# Copy_of_Prophesse_Sensor_v_1_5.net
KiCad netlist of a schematic drawn in Altium Designer
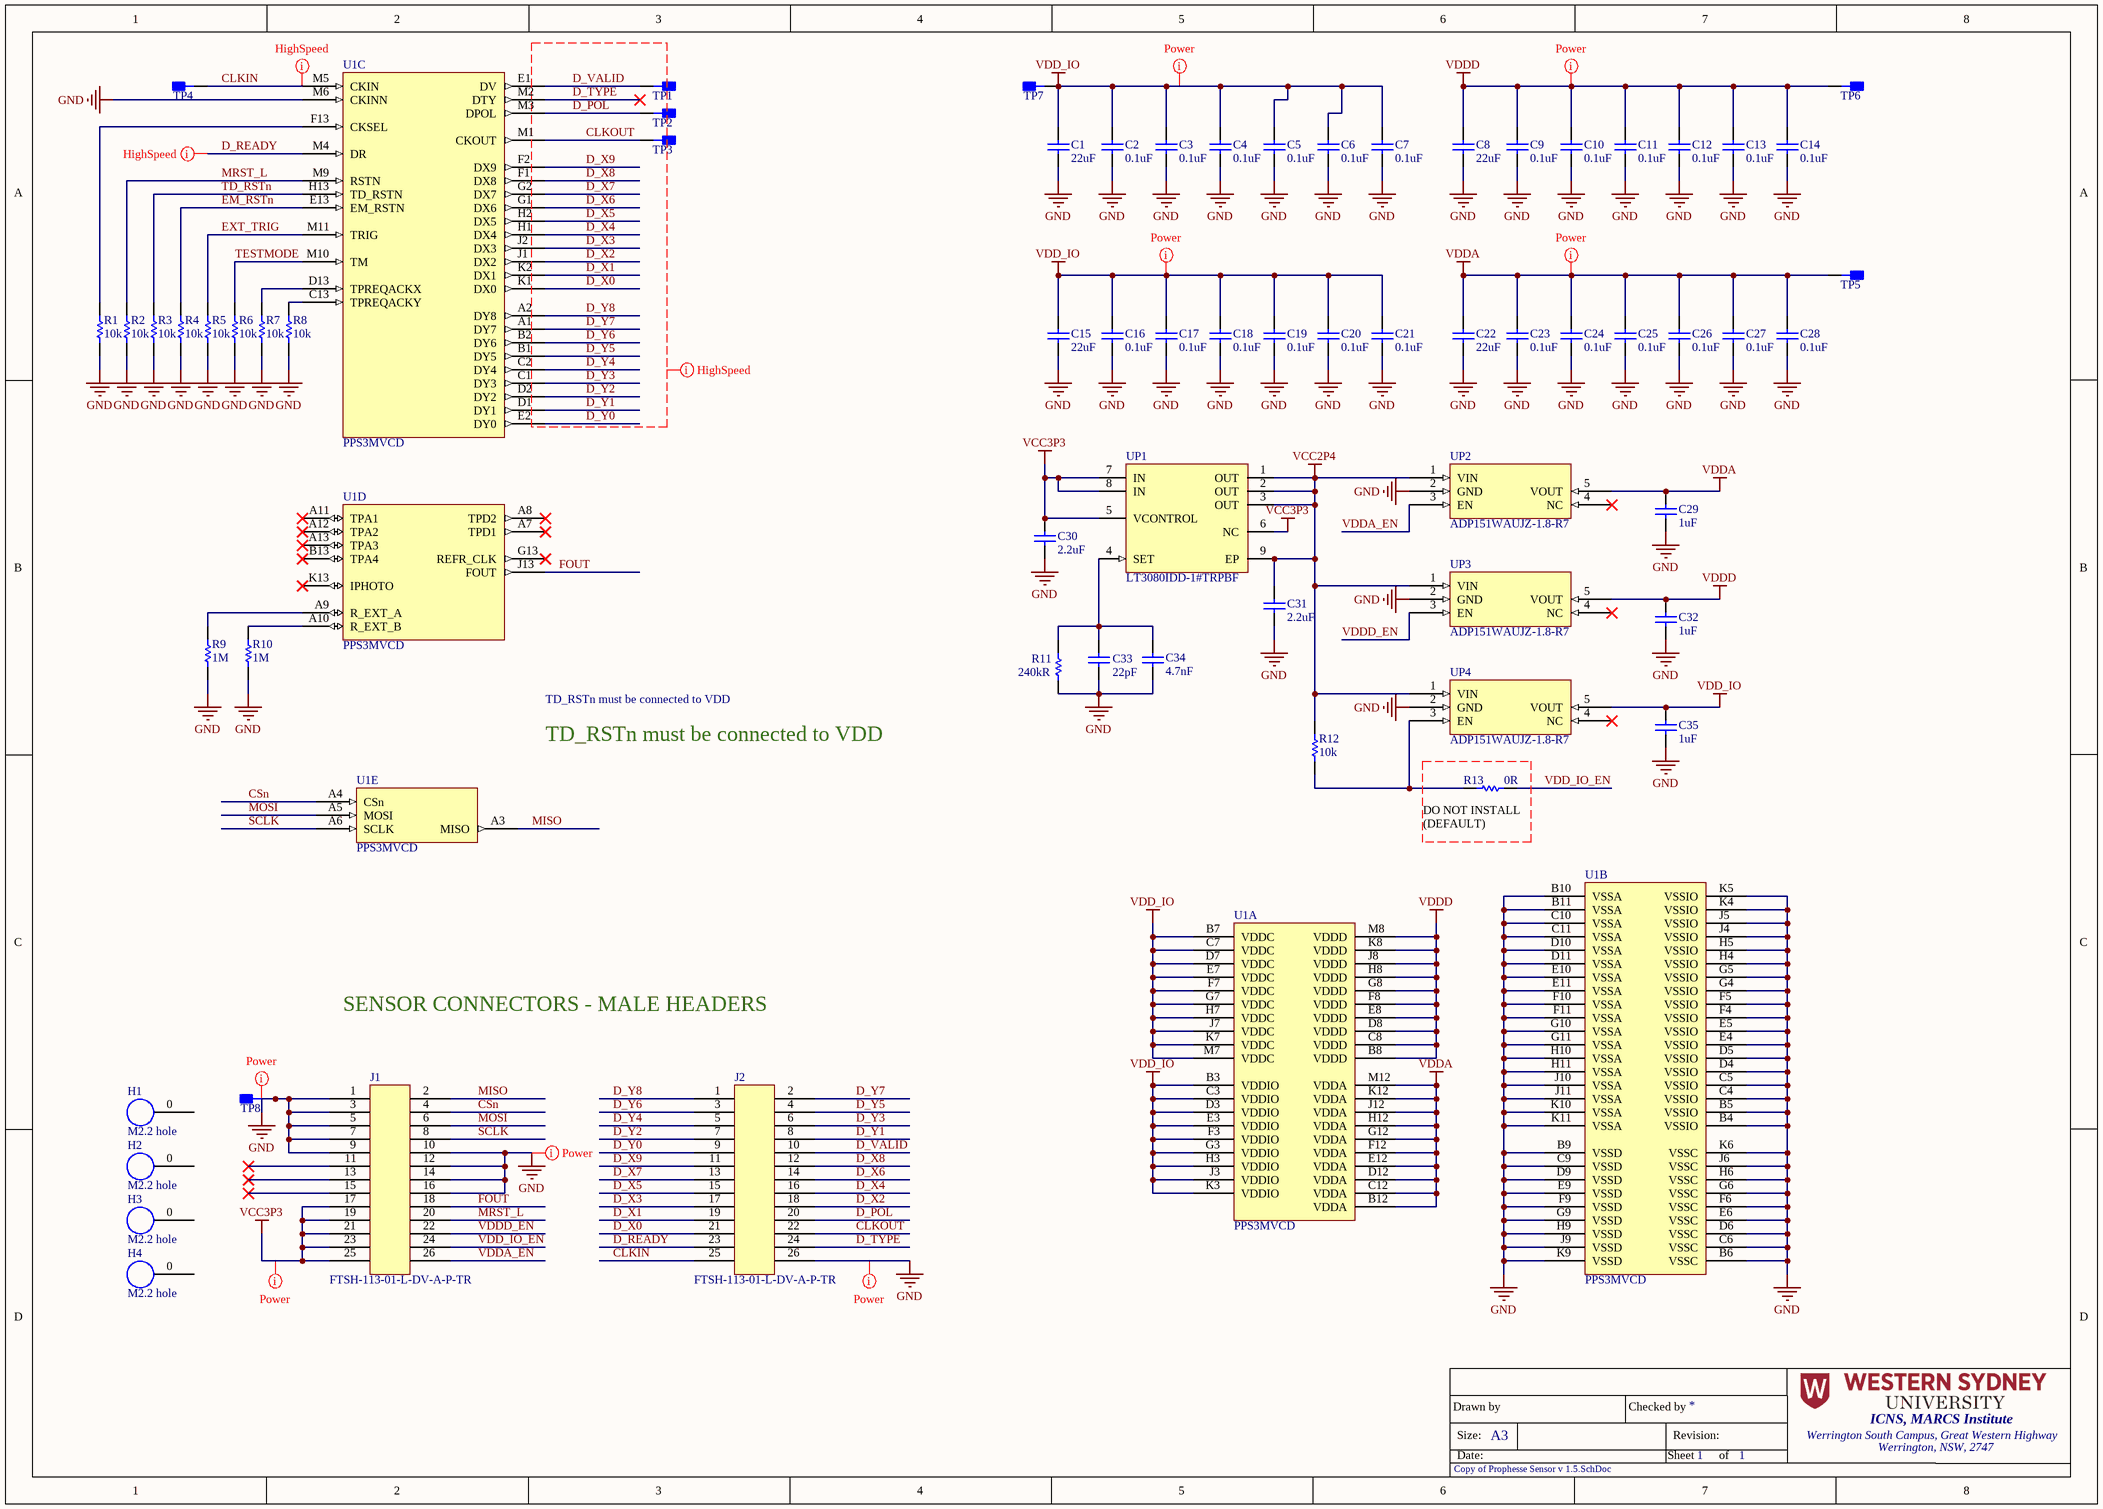
[diagram p0: Copy of Prophesse Sensor v 1.5.SchDoc]

(export (version "E")
  (design (tool "Eeschema 10.0.6"))
  (components
    (comp (ref "C1")
      (value "22uF")
      (footprint "CAP 0603 (1608)")
      (fields
        (field (name "MANUFACTURER") "Taiyo Yuden")
        (field (name "MANUFACTURER PART NUMBER") "LMK107BBJ226MA-T")
      )
      (libsource (lib "Falcon_Neuro") (part "LMK107BBJ226MA-T"))
    )
    (comp (ref "C2")
      (value "0.1uF")
      (footprint "CAP 0201 (0603)")
      (description "C0201C104K9PACTU, 0.1µF ±10% 6.3V Ceramic Capacitor X5R 0201 (0603 Metric)")
      (fields
        (field (name "MANUFACTURER") "KENET")
        (field (name "MANUFACTURER PART NUMBER") "C0201C104K9PACTU")
      )
      (libsource (lib "Falcon_Neuro") (part "C0201C104K9PACTU"))
    )
    (comp (ref "C3")
      (value "0.1uF")
      (footprint "CAP 0201 (0603)")
      (description "C0201C104K9PACTU, 0.1µF ±10% 6.3V Ceramic Capacitor X5R 0201 (0603 Metric)")
      (fields
        (field (name "MANUFACTURER") "KENET")
        (field (name "MANUFACTURER PART NUMBER") "C0201C104K9PACTU")
      )
      (libsource (lib "Falcon_Neuro") (part "C0201C104K9PACTU"))
    )
    (comp (ref "C4")
      (value "0.1uF")
      (footprint "CAP 0201 (0603)")
      (description "C0201C104K9PACTU, 0.1µF ±10% 6.3V Ceramic Capacitor X5R 0201 (0603 Metric)")
      (fields
        (field (name "MANUFACTURER") "KENET")
        (field (name "MANUFACTURER PART NUMBER") "C0201C104K9PACTU")
      )
      (libsource (lib "Falcon_Neuro") (part "C0201C104K9PACTU"))
    )
    (comp (ref "C5")
      (value "0.1uF")
      (footprint "CAP 0201 (0603)")
      (description "C0201C104K9PACTU, 0.1µF ±10% 6.3V Ceramic Capacitor X5R 0201 (0603 Metric)")
      (fields
        (field (name "MANUFACTURER") "KENET")
        (field (name "MANUFACTURER PART NUMBER") "C0201C104K9PACTU")
      )
      (libsource (lib "Falcon_Neuro") (part "C0201C104K9PACTU"))
    )
    (comp (ref "C6")
      (value "0.1uF")
      (footprint "CAP 0201 (0603)")
      (description "C0201C104K9PACTU, 0.1µF ±10% 6.3V Ceramic Capacitor X5R 0201 (0603 Metric)")
      (fields
        (field (name "MANUFACTURER") "KENET")
        (field (name "MANUFACTURER PART NUMBER") "C0201C104K9PACTU")
      )
      (libsource (lib "Falcon_Neuro") (part "C0201C104K9PACTU"))
    )
    (comp (ref "C7")
      (value "0.1uF")
      (footprint "CAP 0201 (0603)")
      (description "C0201C104K9PACTU, 0.1µF ±10% 6.3V Ceramic Capacitor X5R 0201 (0603 Metric)")
      (fields
        (field (name "MANUFACTURER") "KENET")
        (field (name "MANUFACTURER PART NUMBER") "C0201C104K9PACTU")
      )
      (libsource (lib "Falcon_Neuro") (part "C0201C104K9PACTU"))
    )
    (comp (ref "C8")
      (value "22uF")
      (footprint "CAP 0603 (1608)")
      (fields
        (field (name "MANUFACTURER") "Taiyo Yuden")
        (field (name "MANUFACTURER PART NUMBER") "LMK107BBJ226MA-T")
      )
      (libsource (lib "Falcon_Neuro") (part "LMK107BBJ226MA-T"))
    )
    (comp (ref "C9")
      (value "0.1uF")
      (footprint "CAP 0201 (0603)")
      (description "C0201C104K9PACTU, 0.1µF ±10% 6.3V Ceramic Capacitor X5R 0201 (0603 Metric)")
      (fields
        (field (name "MANUFACTURER") "KENET")
        (field (name "MANUFACTURER PART NUMBER") "C0201C104K9PACTU")
      )
      (libsource (lib "Falcon_Neuro") (part "C0201C104K9PACTU"))
    )
    (comp (ref "C10")
      (value "0.1uF")
      (footprint "CAP 0201 (0603)")
      (description "C0201C104K9PACTU, 0.1µF ±10% 6.3V Ceramic Capacitor X5R 0201 (0603 Metric)")
      (fields
        (field (name "MANUFACTURER") "KENET")
        (field (name "MANUFACTURER PART NUMBER") "C0201C104K9PACTU")
      )
      (libsource (lib "Falcon_Neuro") (part "C0201C104K9PACTU"))
    )
    (comp (ref "C11")
      (value "0.1uF")
      (footprint "CAP 0201 (0603)")
      (description "C0201C104K9PACTU, 0.1µF ±10% 6.3V Ceramic Capacitor X5R 0201 (0603 Metric)")
      (fields
        (field (name "MANUFACTURER") "KENET")
        (field (name "MANUFACTURER PART NUMBER") "C0201C104K9PACTU")
      )
      (libsource (lib "Falcon_Neuro") (part "C0201C104K9PACTU"))
    )
    (comp (ref "C12")
      (value "0.1uF")
      (footprint "CAP 0201 (0603)")
      (description "C0201C104K9PACTU, 0.1µF ±10% 6.3V Ceramic Capacitor X5R 0201 (0603 Metric)")
      (fields
        (field (name "MANUFACTURER") "KENET")
        (field (name "MANUFACTURER PART NUMBER") "C0201C104K9PACTU")
      )
      (libsource (lib "Falcon_Neuro") (part "C0201C104K9PACTU"))
    )
    (comp (ref "C13")
      (value "0.1uF")
      (footprint "CAP 0201 (0603)")
      (description "C0201C104K9PACTU, 0.1µF ±10% 6.3V Ceramic Capacitor X5R 0201 (0603 Metric)")
      (fields
        (field (name "MANUFACTURER") "KENET")
        (field (name "MANUFACTURER PART NUMBER") "C0201C104K9PACTU")
      )
      (libsource (lib "Falcon_Neuro") (part "C0201C104K9PACTU"))
    )
    (comp (ref "C14")
      (value "0.1uF")
      (footprint "CAP 0201 (0603)")
      (description "C0201C104K9PACTU, 0.1µF ±10% 6.3V Ceramic Capacitor X5R 0201 (0603 Metric)")
      (fields
        (field (name "MANUFACTURER") "KENET")
        (field (name "MANUFACTURER PART NUMBER") "C0201C104K9PACTU")
      )
      (libsource (lib "Falcon_Neuro") (part "C0201C104K9PACTU"))
    )
    (comp (ref "C15")
      (value "22uF")
      (footprint "CAP 0603 (1608)")
      (fields
        (field (name "MANUFACTURER") "Taiyo Yuden")
        (field (name "MANUFACTURER PART NUMBER") "LMK107BBJ226MA-T")
      )
      (libsource (lib "Falcon_Neuro") (part "LMK107BBJ226MA-T"))
    )
    (comp (ref "C16")
      (value "0.1uF")
      (footprint "CAP 0201 (0603)")
      (description "C0201C104K9PACTU, 0.1µF ±10% 6.3V Ceramic Capacitor X5R 0201 (0603 Metric)")
      (fields
        (field (name "MANUFACTURER") "KENET")
        (field (name "MANUFACTURER PART NUMBER") "C0201C104K9PACTU")
      )
      (libsource (lib "Falcon_Neuro") (part "C0201C104K9PACTU"))
    )
    (comp (ref "C17")
      (value "0.1uF")
      (footprint "CAP 0201 (0603)")
      (description "C0201C104K9PACTU, 0.1µF ±10% 6.3V Ceramic Capacitor X5R 0201 (0603 Metric)")
      (fields
        (field (name "MANUFACTURER") "KENET")
        (field (name "MANUFACTURER PART NUMBER") "C0201C104K9PACTU")
      )
      (libsource (lib "Falcon_Neuro") (part "C0201C104K9PACTU"))
    )
    (comp (ref "C18")
      (value "0.1uF")
      (footprint "CAP 0201 (0603)")
      (description "C0201C104K9PACTU, 0.1µF ±10% 6.3V Ceramic Capacitor X5R 0201 (0603 Metric)")
      (fields
        (field (name "MANUFACTURER") "KENET")
        (field (name "MANUFACTURER PART NUMBER") "C0201C104K9PACTU")
      )
      (libsource (lib "Falcon_Neuro") (part "C0201C104K9PACTU"))
    )
    (comp (ref "C19")
      (value "0.1uF")
      (footprint "CAP 0201 (0603)")
      (description "C0201C104K9PACTU, 0.1µF ±10% 6.3V Ceramic Capacitor X5R 0201 (0603 Metric)")
      (fields
        (field (name "MANUFACTURER") "KENET")
        (field (name "MANUFACTURER PART NUMBER") "C0201C104K9PACTU")
      )
      (libsource (lib "Falcon_Neuro") (part "C0201C104K9PACTU"))
    )
    (comp (ref "C20")
      (value "0.1uF")
      (footprint "CAP 0201 (0603)")
      (description "C0201C104K9PACTU, 0.1µF ±10% 6.3V Ceramic Capacitor X5R 0201 (0603 Metric)")
      (fields
        (field (name "MANUFACTURER") "KENET")
        (field (name "MANUFACTURER PART NUMBER") "C0201C104K9PACTU")
      )
      (libsource (lib "Falcon_Neuro") (part "C0201C104K9PACTU"))
    )
    (comp (ref "C21")
      (value "0.1uF")
      (footprint "CAP 0201 (0603)")
      (description "C0201C104K9PACTU, 0.1µF ±10% 6.3V Ceramic Capacitor X5R 0201 (0603 Metric)")
      (fields
        (field (name "MANUFACTURER") "KENET")
        (field (name "MANUFACTURER PART NUMBER") "C0201C104K9PACTU")
      )
      (libsource (lib "Falcon_Neuro") (part "C0201C104K9PACTU"))
    )
    (comp (ref "C22")
      (value "22uF")
      (footprint "CAP 0603 (1608)")
      (fields
        (field (name "MANUFACTURER") "Taiyo Yuden")
        (field (name "MANUFACTURER PART NUMBER") "LMK107BBJ226MA-T")
      )
      (libsource (lib "Falcon_Neuro") (part "LMK107BBJ226MA-T"))
    )
    (comp (ref "C23")
      (value "0.1uF")
      (footprint "CAP 0201 (0603)")
      (description "C0201C104K9PACTU, 0.1µF ±10% 6.3V Ceramic Capacitor X5R 0201 (0603 Metric)")
      (fields
        (field (name "MANUFACTURER") "KENET")
        (field (name "MANUFACTURER PART NUMBER") "C0201C104K9PACTU")
      )
      (libsource (lib "Falcon_Neuro") (part "C0201C104K9PACTU"))
    )
    (comp (ref "C24")
      (value "0.1uF")
      (footprint "CAP 0201 (0603)")
      (description "C0201C104K9PACTU, 0.1µF ±10% 6.3V Ceramic Capacitor X5R 0201 (0603 Metric)")
      (fields
        (field (name "MANUFACTURER") "KENET")
        (field (name "MANUFACTURER PART NUMBER") "C0201C104K9PACTU")
      )
      (libsource (lib "Falcon_Neuro") (part "C0201C104K9PACTU"))
    )
    (comp (ref "C25")
      (value "0.1uF")
      (footprint "CAP 0201 (0603)")
      (description "C0201C104K9PACTU, 0.1µF ±10% 6.3V Ceramic Capacitor X5R 0201 (0603 Metric)")
      (fields
        (field (name "MANUFACTURER") "KENET")
        (field (name "MANUFACTURER PART NUMBER") "C0201C104K9PACTU")
      )
      (libsource (lib "Falcon_Neuro") (part "C0201C104K9PACTU"))
    )
    (comp (ref "C26")
      (value "0.1uF")
      (footprint "CAP 0201 (0603)")
      (description "C0201C104K9PACTU, 0.1µF ±10% 6.3V Ceramic Capacitor X5R 0201 (0603 Metric)")
      (fields
        (field (name "MANUFACTURER") "KENET")
        (field (name "MANUFACTURER PART NUMBER") "C0201C104K9PACTU")
      )
      (libsource (lib "Falcon_Neuro") (part "C0201C104K9PACTU"))
    )
    (comp (ref "C27")
      (value "0.1uF")
      (footprint "CAP 0201 (0603)")
      (description "C0201C104K9PACTU, 0.1µF ±10% 6.3V Ceramic Capacitor X5R 0201 (0603 Metric)")
      (fields
        (field (name "MANUFACTURER") "KENET")
        (field (name "MANUFACTURER PART NUMBER") "C0201C104K9PACTU")
      )
      (libsource (lib "Falcon_Neuro") (part "C0201C104K9PACTU"))
    )
    (comp (ref "C28")
      (value "0.1uF")
      (footprint "CAP 0201 (0603)")
      (description "C0201C104K9PACTU, 0.1µF ±10% 6.3V Ceramic Capacitor X5R 0201 (0603 Metric)")
      (fields
        (field (name "MANUFACTURER") "KENET")
        (field (name "MANUFACTURER PART NUMBER") "C0201C104K9PACTU")
      )
      (libsource (lib "Falcon_Neuro") (part "C0201C104K9PACTU"))
    )
    (comp (ref "C29")
      (value "1uF")
      (footprint "CAP 0201 (0603)")
      (description "GRM033R60J105MEA2D, 1µF ±20% 6.3V Ceramic Capacitor X5R 0201 (0603 Metric)")
      (fields
        (field (name "MANUFACTURER") "Murata Electronics")
        (field (name "MANUFACTURER PART NUMBER") "GRM033R60J105MEA2D")
      )
      (libsource (lib "Falcon_Neuro") (part "GRM033R60J105MEA2D"))
    )
    (comp (ref "C30")
      (value "2.2uF")
      (footprint "CAP 0402 (1005)")
      (description "C0402C225K9PAC7867, 2.2µF ±10% 6.3V Ceramic Capacitor X5R 0402 (1005 Metric)")
      (fields
        (field (name "MANUFACTURER") "KEMET")
        (field (name "MANUFACTURER PART NUMBER") "C0402C225K9PAC7867")
      )
      (libsource (lib "Falcon_Neuro") (part "C0402C225K9PAC7867"))
    )
    (comp (ref "C31")
      (value "2.2uF")
      (footprint "CAP 0402 (1005)")
      (description "C0402C225K9PAC7867, 2.2µF ±10% 6.3V Ceramic Capacitor X5R 0402 (1005 Metric)")
      (fields
        (field (name "MANUFACTURER") "KEMET")
        (field (name "MANUFACTURER PART NUMBER") "C0402C225K9PAC7867")
      )
      (libsource (lib "Falcon_Neuro") (part "C0402C225K9PAC7867"))
    )
    (comp (ref "C32")
      (value "1uF")
      (footprint "CAP 0201 (0603)")
      (description "GRM033R60J105MEA2D, 1µF ±20% 6.3V Ceramic Capacitor X5R 0201 (0603 Metric)")
      (fields
        (field (name "MANUFACTURER") "Murata Electronics")
        (field (name "MANUFACTURER PART NUMBER") "GRM033R60J105MEA2D")
      )
      (libsource (lib "Falcon_Neuro") (part "GRM033R60J105MEA2D"))
    )
    (comp (ref "C33")
      (value "GRM1885C1H220JA01D")
      (footprint "CAP 0603 (1608)")
      (description "CAP CER 22PF 50V C0G/NP0 0603")
      (fields
        (field (name "MANUFACTURER") "Murata")
        (field (name "CAPACITANCE") "22pF")
        (field (name "TOLERANCE") "10%")
      )
      (libsource (lib "Falcon_Neuro") (part "GRM1885C1H220JA01D"))
    )
    (comp (ref "C34")
      (value "4.7nF")
      (footprint "CAP 0201 (0603)")
      (description "CC0201KRX7R6BB472, 4700pF ±10% 10V Ceramic Capacitor X7R 0201 (0603 Metric)")
      (fields
        (field (name "MANUFACTURER") "Yageo")
        (field (name "MANUFACTURER PART NUMBER") "CC0201KRX7R6BB472")
      )
      (libsource (lib "Falcon_Neuro") (part "CC0201KRX7R6BB472"))
    )
    (comp (ref "C35")
      (value "1uF")
      (footprint "CAP 0201 (0603)")
      (description "GRM033R60J105MEA2D, 1µF ±20% 6.3V Ceramic Capacitor X5R 0201 (0603 Metric)")
      (fields
        (field (name "MANUFACTURER") "Murata Electronics")
        (field (name "MANUFACTURER PART NUMBER") "GRM033R60J105MEA2D")
      )
      (libsource (lib "Falcon_Neuro") (part "GRM033R60J105MEA2D"))
    )
    (comp (ref "H1")
      (value "M2.2 hole")
      (footprint "M2.2 hole")
      (description "M2.2 through hole not plated")
      (libsource (lib "Falcon_Neuro") (part "M2.2 hole"))
    )
    (comp (ref "H2")
      (value "M2.2 hole")
      (footprint "M2.2 hole")
      (description "M2.2 through hole not plated")
      (libsource (lib "Falcon_Neuro") (part "M2.2 hole"))
    )
    (comp (ref "H3")
      (value "M2.2 hole")
      (footprint "M2.2 hole")
      (description "M2.2 through hole not plated")
      (libsource (lib "Falcon_Neuro") (part "M2.2 hole"))
    )
    (comp (ref "H4")
      (value "M2.2 hole")
      (footprint "M2.2 hole")
      (description "M2.2 through hole not plated")
      (libsource (lib "Falcon_Neuro") (part "M2.2 hole"))
    )
    (comp (ref "J1")
      (value "FTSH-113-01-L-DV-A-P-TR")
      (footprint "FTSH-113-01-L-DV-A")
      (description "Connector Header Surface Mount 26 position 0.050\" (1.27mm) 2 Rows Alignment Pin")
      (fields (field (name "MANUFACTURER") "Samtec"))
      (libsource (lib "Falcon_Neuro") (part "FTSH-113-01-L-DV-A-P-TR"))
    )
    (comp (ref "J2")
      (value "FTSH-113-01-L-DV-A-P-TR")
      (footprint "FTSH-113-01-L-DV-A")
      (description "Connector Header Surface Mount 26 position 0.050\" (1.27mm) 2 Rows Alignment Pin")
      (fields (field (name "MANUFACTURER") "Samtec"))
      (libsource (lib "Falcon_Neuro") (part "FTSH-113-01-L-DV-A-P-TR"))
    )
    (comp (ref "R1")
      (value "10k")
      (footprint "RES 0201 (0603)")
      (fields
        (field (name "MANUFACTURER PART NUMBER") "RK73H1HTTC1002F")
        (field (name "MANUFACTURER") "KOA Speer Electronics, Inc.")
      )
      (libsource (lib "Falcon_Neuro") (part "RK73H1HTTC1002F"))
    )
    (comp (ref "R2")
      (value "10k")
      (footprint "RES 0201 (0603)")
      (fields
        (field (name "MANUFACTURER PART NUMBER") "RK73H1HTTC1002F")
        (field (name "MANUFACTURER") "KOA Speer Electronics, Inc.")
      )
      (libsource (lib "Falcon_Neuro") (part "RK73H1HTTC1002F"))
    )
    (comp (ref "R3")
      (value "10k")
      (footprint "RES 0201 (0603)")
      (fields
        (field (name "MANUFACTURER PART NUMBER") "RK73H1HTTC1002F")
        (field (name "MANUFACTURER") "KOA Speer Electronics, Inc.")
      )
      (libsource (lib "Falcon_Neuro") (part "RK73H1HTTC1002F"))
    )
    (comp (ref "R4")
      (value "10k")
      (footprint "RES 0201 (0603)")
      (fields
        (field (name "MANUFACTURER PART NUMBER") "RK73H1HTTC1002F")
        (field (name "MANUFACTURER") "KOA Speer Electronics, Inc.")
      )
      (libsource (lib "Falcon_Neuro") (part "RK73H1HTTC1002F"))
    )
    (comp (ref "R5")
      (value "10k")
      (footprint "RES 0201 (0603)")
      (fields
        (field (name "MANUFACTURER PART NUMBER") "RK73H1HTTC1002F")
        (field (name "MANUFACTURER") "KOA Speer Electronics, Inc.")
      )
      (libsource (lib "Falcon_Neuro") (part "RK73H1HTTC1002F"))
    )
    (comp (ref "R6")
      (value "10k")
      (footprint "RES 0201 (0603)")
      (fields
        (field (name "MANUFACTURER PART NUMBER") "RK73H1HTTC1002F")
        (field (name "MANUFACTURER") "KOA Speer Electronics, Inc.")
      )
      (libsource (lib "Falcon_Neuro") (part "RK73H1HTTC1002F"))
    )
    (comp (ref "R7")
      (value "10k")
      (footprint "RES 0201 (0603)")
      (fields
        (field (name "MANUFACTURER PART NUMBER") "RK73H1HTTC1002F")
        (field (name "MANUFACTURER") "KOA Speer Electronics, Inc.")
      )
      (libsource (lib "Falcon_Neuro") (part "RK73H1HTTC1002F"))
    )
    (comp (ref "R8")
      (value "10k")
      (footprint "RES 0201 (0603)")
      (fields
        (field (name "MANUFACTURER PART NUMBER") "RK73H1HTTC1002F")
        (field (name "MANUFACTURER") "KOA Speer Electronics, Inc.")
      )
      (libsource (lib "Falcon_Neuro") (part "RK73H1HTTC1002F"))
    )
    (comp (ref "R9")
      (value "1M")
      (footprint "RES 0402 (1005)")
      (fields
        (field (name "MANUFACTURER PART NUMBER") "CRCW04021M00DHEDP")
        (field (name "MANUFACTURER") "Vishay Dale")
      )
      (libsource (lib "Falcon_Neuro") (part "CRCW04021M00DHEDP"))
    )
    (comp (ref "R10")
      (value "1M")
      (footprint "RES 0402 (1005)")
      (fields
        (field (name "MANUFACTURER PART NUMBER") "CRCW04021M00DHEDP")
        (field (name "MANUFACTURER") "Vishay Dale")
      )
      (libsource (lib "Falcon_Neuro") (part "CRCW04021M00DHEDP"))
    )
    (comp (ref "R11")
      (value "ERA-3AEB244V")
      (footprint "RES 0603 (1608)")
      (description "Res Thin Film 0603 240K Ohm 0.1% 1/10W ±25ppm/°C Molded SMD SMD Punched Carrier T/R")
      (fields
        (field (name "MANUFACTURER") "Panasonic")
        (field (name "TOLERANCE") "0.1%")
        (field (name "RESISTANCE") "240kR")
      )
      (libsource (lib "Falcon_Neuro") (part "ERA-3AEB244V"))
    )
    (comp (ref "R12")
      (value "10k")
      (footprint "RES 0201 (0603)")
      (fields
        (field (name "MANUFACTURER PART NUMBER") "RK73H1HTTC1002F")
        (field (name "MANUFACTURER") "KOA Speer Electronics, Inc.")
      )
      (libsource (lib "Falcon_Neuro") (part "RK73H1HTTC1002F"))
    )
    (comp (ref "R13")
      (value "0R")
      (footprint "RES 0402 (1005)")
      (fields
        (field (name "MANUFACTURER PART NUMBER") "RK73Z1ETTP")
        (field (name "MANUFACTURER") "KOA Speer Electronics, Inc.")
      )
      (libsource (lib "Falcon_Neuro") (part "RK73Z1ETTP"))
    )
    (comp (ref "TP1")
      (value "5015")
      (footprint "FP-5015-MFG")
      (description "PC TEST POINT MINIATURE SMT")
      (fields (field (name "MANUFACTURER") "Keystone Electronics"))
      (libsource (lib "Falcon_Neuro") (part "5015"))
    )
    (comp (ref "TP2")
      (value "5015")
      (footprint "FP-5015-MFG")
      (description "PC TEST POINT MINIATURE SMT")
      (fields (field (name "MANUFACTURER") "Keystone Electronics"))
      (libsource (lib "Falcon_Neuro") (part "5015"))
    )
    (comp (ref "TP3")
      (value "5015")
      (footprint "FP-5015-MFG")
      (description "PC TEST POINT MINIATURE SMT")
      (fields (field (name "MANUFACTURER") "Keystone Electronics"))
      (libsource (lib "Falcon_Neuro") (part "5015"))
    )
    (comp (ref "TP4")
      (value "5015")
      (footprint "FP-5015-MFG")
      (description "PC TEST POINT MINIATURE SMT")
      (fields (field (name "MANUFACTURER") "Keystone Electronics"))
      (libsource (lib "") (part "5015_1"))
    )
    (comp (ref "TP5")
      (value "5015")
      (footprint "FP-5015-MFG")
      (description "PC TEST POINT MINIATURE SMT")
      (fields (field (name "MANUFACTURER") "Keystone Electronics"))
      (libsource (lib "Falcon_Neuro") (part "5015"))
    )
    (comp (ref "TP6")
      (value "5015")
      (footprint "FP-5015-MFG")
      (description "PC TEST POINT MINIATURE SMT")
      (fields (field (name "MANUFACTURER") "Keystone Electronics"))
      (libsource (lib "Falcon_Neuro") (part "5015"))
    )
    (comp (ref "TP7")
      (value "5015")
      (footprint "FP-5015-MFG")
      (description "PC TEST POINT MINIATURE SMT")
      (fields (field (name "MANUFACTURER") "Keystone Electronics"))
      (libsource (lib "") (part "5015_1"))
    )
    (comp (ref "TP8")
      (value "5015")
      (footprint "FP-5015-MFG")
      (description "PC TEST POINT MINIATURE SMT")
      (fields (field (name "MANUFACTURER") "Keystone Electronics"))
      (libsource (lib "") (part "5015_1"))
    )
    (comp (ref "U1")
      (value "PPS3MVCD")
      (footprint "BPGA142C100P13X11_1500X1300X223_PSS3MVCD")
      (description "Prophesse Sensor V3M")
      (fields (field (name "MANUFACTURER") "Prophesse"))
      (libsource (lib "Falcon_Neuro") (part "PPS3MVCD"))
    )
    (comp (ref "UP1")
      (value "LT3080IDD-1#TRPBF")
      (footprint "LT-DD-8_V")
      (description "Linear Voltage Regulator IC Positive Adjustable 1 Output 1.1A 8-DFN (3x3)")
      (fields (field (name "MANUFACTURER") "Analog Devices / Linear Technology"))
      (libsource (lib "ICNS_PropheseeLib") (part "LT3080IDD-1#TRPBF"))
    )
    (comp (ref "UP2")
      (value "ADP151WAUJZ-1.8-R7")
      (footprint "SOT95P280X100-5N")
      (description "LDO Regulator Pos 1.8V 0.2A Automotive 5-Pin TSOT T/R")
      (fields (field (name "MANUFACTURER") "Analog Devices"))
      (libsource (lib "Falcon_Neuro") (part "ADP151WAUJZ-1.8-R7"))
    )
    (comp (ref "UP3")
      (value "ADP151WAUJZ-1.8-R7")
      (footprint "SOT95P280X100-5N")
      (description "LDO Regulator Pos 1.8V 0.2A Automotive 5-Pin TSOT T/R")
      (fields (field (name "MANUFACTURER") "Analog Devices"))
      (libsource (lib "Falcon_Neuro") (part "ADP151WAUJZ-1.8-R7"))
    )
    (comp (ref "UP4")
      (value "ADP151WAUJZ-1.8-R7")
      (footprint "SOT95P280X100-5N")
      (description "LDO Regulator Pos 1.8V 0.2A Automotive 5-Pin TSOT T/R")
      (fields (field (name "MANUFACTURER") "Analog Devices"))
      (libsource (lib "Falcon_Neuro") (part "ADP151WAUJZ-1.8-R7"))
    )
  )
  (nets
    (net (code "1") (name "/CLKIN") (class "Default")
      (node (ref "J2") (pin "25") (pintype "passive"))
      (node (ref "TP4") (pin "1") (pinfunction "1_1") (pintype "passive"))
      (node (ref "U1") (pin "M5") (pinfunction "CKIN_M5") (pintype "input"))
    )
    (net (code "2") (name "/CLKOUT") (class "Default")
      (node (ref "J2") (pin "22") (pintype "passive"))
      (node (ref "TP3") (pin "1") (pinfunction "1_1") (pintype "passive"))
      (node (ref "U1") (pin "M1") (pinfunction "CKOUT_M1") (pintype "output"))
    )
    (net (code "3") (name "/CSn") (class "Default")
      (node (ref "J1") (pin "4") (pintype "passive"))
      (node (ref "U1") (pin "A4") (pinfunction "CSn_A4") (pintype "input"))
    )
    (net (code "4") (name "/D_POL") (class "Default")
      (node (ref "J2") (pin "20") (pintype "passive"))
      (node (ref "TP2") (pin "1") (pinfunction "1_1") (pintype "passive"))
      (node (ref "U1") (pin "M3") (pinfunction "DPOL_M3") (pintype "output"))
    )
    (net (code "5") (name "/D_READY") (class "Default")
      (node (ref "J2") (pin "23") (pintype "passive"))
      (node (ref "U1") (pin "M4") (pinfunction "DR_M4") (pintype "input"))
    )
    (net (code "6") (name "/D_TYPE") (class "Default")
      (node (ref "J2") (pin "24") (pintype "passive"))
      (node (ref "U1") (pin "M2") (pinfunction "DTY_M2") (pintype "output"))
    )
    (net (code "7") (name "/D_VALID") (class "Default")
      (node (ref "J2") (pin "10") (pintype "passive"))
      (node (ref "TP1") (pin "1") (pinfunction "1_1") (pintype "passive"))
      (node (ref "U1") (pin "E1") (pinfunction "DV_E1") (pintype "output"))
    )
    (net (code "8") (name "/D_X0") (class "Default")
      (node (ref "J2") (pin "21") (pintype "passive"))
      (node (ref "U1") (pin "K1") (pinfunction "DX0_K1") (pintype "output"))
    )
    (net (code "9") (name "/D_X1") (class "Default")
      (node (ref "J2") (pin "19") (pintype "passive"))
      (node (ref "U1") (pin "K2") (pinfunction "DX1_K2") (pintype "output"))
    )
    (net (code "10") (name "/D_X2") (class "Default")
      (node (ref "J2") (pin "18") (pintype "passive"))
      (node (ref "U1") (pin "J1") (pinfunction "DX2_J1") (pintype "output"))
    )
    (net (code "11") (name "/D_X3") (class "Default")
      (node (ref "J2") (pin "17") (pintype "passive"))
      (node (ref "U1") (pin "J2") (pinfunction "DX3_J2") (pintype "output"))
    )
    (net (code "12") (name "/D_X4") (class "Default")
      (node (ref "J2") (pin "16") (pintype "passive"))
      (node (ref "U1") (pin "H1") (pinfunction "DX4_H1") (pintype "output"))
    )
    (net (code "13") (name "/D_X5") (class "Default")
      (node (ref "J2") (pin "15") (pintype "passive"))
      (node (ref "U1") (pin "H2") (pinfunction "DX5_H2") (pintype "output"))
    )
    (net (code "14") (name "/D_X6") (class "Default")
      (node (ref "J2") (pin "14") (pintype "passive"))
      (node (ref "U1") (pin "G1") (pinfunction "DX6_G1") (pintype "output"))
    )
    (net (code "15") (name "/D_X7") (class "Default")
      (node (ref "J2") (pin "13") (pintype "passive"))
      (node (ref "U1") (pin "G2") (pinfunction "DX7_G2") (pintype "output"))
    )
    (net (code "16") (name "/D_X8") (class "Default")
      (node (ref "J2") (pin "12") (pintype "passive"))
      (node (ref "U1") (pin "F1") (pinfunction "DX8_F1") (pintype "output"))
    )
    (net (code "17") (name "/D_X9") (class "Default")
      (node (ref "J2") (pin "11") (pintype "passive"))
      (node (ref "U1") (pin "F2") (pinfunction "DX9_F2") (pintype "output"))
    )
    (net (code "18") (name "/D_Y0") (class "Default")
      (node (ref "J2") (pin "9") (pintype "passive"))
      (node (ref "U1") (pin "E2") (pinfunction "DY0_E2") (pintype "output"))
    )
    (net (code "19") (name "/D_Y1") (class "Default")
      (node (ref "J2") (pin "8") (pintype "passive"))
      (node (ref "U1") (pin "D1") (pinfunction "DY1_D1") (pintype "output"))
    )
    (net (code "20") (name "/D_Y2") (class "Default")
      (node (ref "J2") (pin "7") (pintype "passive"))
      (node (ref "U1") (pin "D2") (pinfunction "DY2_D2") (pintype "output"))
    )
    (net (code "21") (name "/D_Y3") (class "Default")
      (node (ref "J2") (pin "6") (pintype "passive"))
      (node (ref "U1") (pin "C1") (pinfunction "DY3_C1") (pintype "output"))
    )
    (net (code "22") (name "/D_Y4") (class "Default")
      (node (ref "J2") (pin "5") (pintype "passive"))
      (node (ref "U1") (pin "C2") (pinfunction "DY4_C2") (pintype "output"))
    )
    (net (code "23") (name "/D_Y5") (class "Default")
      (node (ref "J2") (pin "4") (pintype "passive"))
      (node (ref "U1") (pin "B1") (pinfunction "DY5_B1") (pintype "output"))
    )
    (net (code "24") (name "/D_Y6") (class "Default")
      (node (ref "J2") (pin "3") (pintype "passive"))
      (node (ref "U1") (pin "B2") (pinfunction "DY6_B2") (pintype "output"))
    )
    (net (code "25") (name "/D_Y7") (class "Default")
      (node (ref "J2") (pin "2") (pintype "passive"))
      (node (ref "U1") (pin "A1") (pinfunction "DY7_A1") (pintype "output"))
    )
    (net (code "26") (name "/D_Y8") (class "Default")
      (node (ref "J2") (pin "1") (pintype "passive"))
      (node (ref "U1") (pin "A2") (pinfunction "DY8_A2") (pintype "output"))
    )
    (net (code "27") (name "/EM_RSTn") (class "Default")
      (node (ref "R4") (pin "2") (pinfunction "2_2") (pintype "passive"))
      (node (ref "U1") (pin "E13") (pinfunction "EM_RSTN_E13") (pintype "input"))
    )
    (net (code "28") (name "/EXT_TRIG") (class "Default")
      (node (ref "R5") (pin "2") (pinfunction "2_2") (pintype "passive"))
      (node (ref "U1") (pin "M11") (pinfunction "TRIG_M11") (pintype "input"))
    )
    (net (code "29") (name "/FOUT") (class "Default")
      (node (ref "J1") (pin "18") (pintype "passive"))
      (node (ref "U1") (pin "J13") (pinfunction "FOUT_J13") (pintype "output"))
    )
    (net (code "30") (name "/MISO") (class "Default")
      (node (ref "J1") (pin "2") (pintype "passive"))
      (node (ref "U1") (pin "A3") (pinfunction "MISO_A3") (pintype "output"))
    )
    (net (code "31") (name "/MOSI") (class "Default")
      (node (ref "J1") (pin "6") (pintype "passive"))
      (node (ref "U1") (pin "A5") (pinfunction "MOSI_A5") (pintype "input"))
    )
    (net (code "32") (name "/MRST_L") (class "Default")
      (node (ref "J1") (pin "20") (pintype "passive"))
      (node (ref "R2") (pin "2") (pinfunction "2_2") (pintype "passive"))
      (node (ref "U1") (pin "M9") (pinfunction "RSTN_M9") (pintype "input"))
    )
    (net (code "33") (name "/SCLK") (class "Default")
      (node (ref "J1") (pin "8") (pintype "passive"))
      (node (ref "U1") (pin "A6") (pinfunction "SCLK_A6") (pintype "input"))
    )
    (net (code "34") (name "/TD_RSTn") (class "Default")
      (node (ref "R3") (pin "2") (pinfunction "2_2") (pintype "passive"))
      (node (ref "U1") (pin "H13") (pinfunction "TD_RSTN_H13") (pintype "input"))
    )
    (net (code "35") (name "/TESTMODE") (class "Default")
      (node (ref "R6") (pin "2") (pinfunction "2_2") (pintype "passive"))
      (node (ref "U1") (pin "M10") (pinfunction "TM_M10") (pintype "input"))
    )
    (net (code "36") (name "/VDDA_EN") (class "Default")
      (node (ref "J1") (pin "26") (pintype "passive"))
      (node (ref "UP2") (pin "3") (pinfunction "EN_3") (pintype "input"))
    )
    (net (code "37") (name "/VDDD_EN") (class "Default")
      (node (ref "J1") (pin "22") (pintype "passive"))
      (node (ref "UP3") (pin "3") (pinfunction "EN_3") (pintype "input"))
    )
    (net (code "38") (name "/VDD_IO_EN") (class "Default")
      (node (ref "J1") (pin "24") (pintype "passive"))
      (node (ref "R13") (pin "2") (pinfunction "2_2") (pintype "passive"))
    )
    (net (code "39") (name "GND") (class "Default")
      (node (ref "C1") (pin "1") (pinfunction "1_1") (pintype "passive"))
      (node (ref "C10") (pin "1") (pinfunction "1_1") (pintype "passive"))
      (node (ref "C11") (pin "1") (pinfunction "1_1") (pintype "passive"))
      (node (ref "C12") (pin "1") (pinfunction "1_1") (pintype "passive"))
      (node (ref "C13") (pin "1") (pinfunction "1_1") (pintype "passive"))
      (node (ref "C14") (pin "1") (pinfunction "1_1") (pintype "passive"))
      (node (ref "C15") (pin "1") (pinfunction "1_1") (pintype "passive"))
      (node (ref "C16") (pin "1") (pinfunction "1_1") (pintype "passive"))
      (node (ref "C17") (pin "1") (pinfunction "1_1") (pintype "passive"))
      (node (ref "C18") (pin "1") (pinfunction "1_1") (pintype "passive"))
      (node (ref "C19") (pin "1") (pinfunction "1_1") (pintype "passive"))
      (node (ref "C2") (pin "1") (pinfunction "1_1") (pintype "passive"))
      (node (ref "C20") (pin "1") (pinfunction "1_1") (pintype "passive"))
      (node (ref "C21") (pin "1") (pinfunction "1_1") (pintype "passive"))
      (node (ref "C22") (pin "1") (pinfunction "1_1") (pintype "passive"))
      (node (ref "C23") (pin "1") (pinfunction "1_1") (pintype "passive"))
      (node (ref "C24") (pin "1") (pinfunction "1_1") (pintype "passive"))
      (node (ref "C25") (pin "1") (pinfunction "1_1") (pintype "passive"))
      (node (ref "C26") (pin "1") (pinfunction "1_1") (pintype "passive"))
      (node (ref "C27") (pin "1") (pinfunction "1_1") (pintype "passive"))
      (node (ref "C28") (pin "1") (pinfunction "1_1") (pintype "passive"))
      (node (ref "C29") (pin "1") (pinfunction "1_1") (pintype "passive"))
      (node (ref "C3") (pin "1") (pinfunction "1_1") (pintype "passive"))
      (node (ref "C30") (pin "2") (pinfunction "2_2") (pintype "passive"))
      (node (ref "C31") (pin "2") (pinfunction "2_2") (pintype "passive"))
      (node (ref "C32") (pin "1") (pinfunction "1_1") (pintype "passive"))
      (node (ref "C33") (pin "2") (pinfunction "2_2") (pintype "passive"))
      (node (ref "C34") (pin "2") (pinfunction "2_2") (pintype "passive"))
      (node (ref "C35") (pin "1") (pinfunction "1_1") (pintype "passive"))
      (node (ref "C4") (pin "1") (pinfunction "1_1") (pintype "passive"))
      (node (ref "C5") (pin "1") (pinfunction "1_1") (pintype "passive"))
      (node (ref "C6") (pin "1") (pinfunction "1_1") (pintype "passive"))
      (node (ref "C7") (pin "1") (pinfunction "1_1") (pintype "passive"))
      (node (ref "C8") (pin "1") (pinfunction "1_1") (pintype "passive"))
      (node (ref "C9") (pin "1") (pinfunction "1_1") (pintype "passive"))
      (node (ref "J1") (pin "1") (pintype "passive"))
      (node (ref "J1") (pin "10") (pintype "passive"))
      (node (ref "J1") (pin "12") (pintype "passive"))
      (node (ref "J1") (pin "14") (pintype "passive"))
      (node (ref "J1") (pin "16") (pintype "passive"))
      (node (ref "J1") (pin "3") (pintype "passive"))
      (node (ref "J1") (pin "5") (pintype "passive"))
      (node (ref "J1") (pin "7") (pintype "passive"))
      (node (ref "J1") (pin "9") (pintype "passive"))
      (node (ref "J2") (pin "26") (pintype "passive"))
      (node (ref "R1") (pin "1") (pinfunction "1_1") (pintype "passive"))
      (node (ref "R10") (pin "2") (pinfunction "2_2") (pintype "passive"))
      (node (ref "R11") (pin "2") (pinfunction "2_2") (pintype "passive"))
      (node (ref "R2") (pin "1") (pinfunction "1_1") (pintype "passive"))
      (node (ref "R3") (pin "1") (pinfunction "1_1") (pintype "passive"))
      (node (ref "R4") (pin "1") (pinfunction "1_1") (pintype "passive"))
      (node (ref "R5") (pin "1") (pinfunction "1_1") (pintype "passive"))
      (node (ref "R6") (pin "1") (pinfunction "1_1") (pintype "passive"))
      (node (ref "R7") (pin "1") (pinfunction "1_1") (pintype "passive"))
      (node (ref "R8") (pin "1") (pinfunction "1_1") (pintype "passive"))
      (node (ref "R9") (pin "1") (pinfunction "1_1") (pintype "passive"))
      (node (ref "TP8") (pin "1") (pinfunction "1_1") (pintype "passive"))
      (node (ref "U1") (pin "B10") (pinfunction "VSSA_B10") (pintype "power_in"))
      (node (ref "U1") (pin "B11") (pinfunction "VSSA_B11") (pintype "power_in"))
      (node (ref "U1") (pin "B4") (pinfunction "VSSIO_B4") (pintype "power_in"))
      (node (ref "U1") (pin "B5") (pinfunction "VSSIO_B5") (pintype "power_in"))
      (node (ref "U1") (pin "B6") (pinfunction "VSSC_B6") (pintype "power_in"))
      (node (ref "U1") (pin "B9") (pinfunction "VSSD_B9") (pintype "power_in"))
      (node (ref "U1") (pin "C10") (pinfunction "VSSA_C10") (pintype "power_in"))
      (node (ref "U1") (pin "C11") (pinfunction "VSSA_C11") (pintype "power_in"))
      (node (ref "U1") (pin "C4") (pinfunction "VSSIO_C4") (pintype "power_in"))
      (node (ref "U1") (pin "C5") (pinfunction "VSSIO_C5") (pintype "power_in"))
      (node (ref "U1") (pin "C6") (pinfunction "VSSC_C6") (pintype "power_in"))
      (node (ref "U1") (pin "C9") (pinfunction "VSSD_C9") (pintype "power_in"))
      (node (ref "U1") (pin "D10") (pinfunction "VSSA_D10") (pintype "power_in"))
      (node (ref "U1") (pin "D11") (pinfunction "VSSA_D11") (pintype "power_in"))
      (node (ref "U1") (pin "D4") (pinfunction "VSSIO_D4") (pintype "power_in"))
      (node (ref "U1") (pin "D5") (pinfunction "VSSIO_D5") (pintype "power_in"))
      (node (ref "U1") (pin "D6") (pinfunction "VSSC_D6") (pintype "power_in"))
      (node (ref "U1") (pin "D9") (pinfunction "VSSD_D9") (pintype "power_in"))
      (node (ref "U1") (pin "E10") (pinfunction "VSSA_E10") (pintype "power_in"))
      (node (ref "U1") (pin "E11") (pinfunction "VSSA_E11") (pintype "power_in"))
      (node (ref "U1") (pin "E4") (pinfunction "VSSIO_E4") (pintype "power_in"))
      (node (ref "U1") (pin "E5") (pinfunction "VSSIO_E5") (pintype "power_in"))
      (node (ref "U1") (pin "E6") (pinfunction "VSSC_E6") (pintype "power_in"))
      (node (ref "U1") (pin "E9") (pinfunction "VSSD_E9") (pintype "power_in"))
      (node (ref "U1") (pin "F10") (pinfunction "VSSA_F10") (pintype "power_in"))
      (node (ref "U1") (pin "F11") (pinfunction "VSSA_F11") (pintype "power_in"))
      (node (ref "U1") (pin "F4") (pinfunction "VSSIO_F4") (pintype "power_in"))
      (node (ref "U1") (pin "F5") (pinfunction "VSSIO_F5") (pintype "power_in"))
      (node (ref "U1") (pin "F6") (pinfunction "VSSC_F6") (pintype "power_in"))
      (node (ref "U1") (pin "F9") (pinfunction "VSSD_F9") (pintype "power_in"))
      (node (ref "U1") (pin "G10") (pinfunction "VSSA_G10") (pintype "power_in"))
      (node (ref "U1") (pin "G11") (pinfunction "VSSA_G11") (pintype "power_in"))
      (node (ref "U1") (pin "G4") (pinfunction "VSSIO_G4") (pintype "power_in"))
      (node (ref "U1") (pin "G5") (pinfunction "VSSIO_G5") (pintype "power_in"))
      (node (ref "U1") (pin "G6") (pinfunction "VSSC_G6") (pintype "power_in"))
      (node (ref "U1") (pin "G9") (pinfunction "VSSD_G9") (pintype "power_in"))
      (node (ref "U1") (pin "H10") (pinfunction "VSSA_H10") (pintype "power_in"))
      (node (ref "U1") (pin "H11") (pinfunction "VSSA_H11") (pintype "power_in"))
      (node (ref "U1") (pin "H4") (pinfunction "VSSIO_H4") (pintype "power_in"))
      (node (ref "U1") (pin "H5") (pinfunction "VSSIO_H5") (pintype "power_in"))
      (node (ref "U1") (pin "H6") (pinfunction "VSSC_H6") (pintype "power_in"))
      (node (ref "U1") (pin "H9") (pinfunction "VSSD_H9") (pintype "power_in"))
      (node (ref "U1") (pin "J10") (pinfunction "VSSA_J10") (pintype "power_in"))
      (node (ref "U1") (pin "J11") (pinfunction "VSSA_J11") (pintype "power_in"))
      (node (ref "U1") (pin "J4") (pinfunction "VSSIO_J4") (pintype "power_in"))
      (node (ref "U1") (pin "J5") (pinfunction "VSSIO_J5") (pintype "power_in"))
      (node (ref "U1") (pin "J6") (pinfunction "VSSC_J6") (pintype "power_in"))
      (node (ref "U1") (pin "J9") (pinfunction "VSSD_J9") (pintype "power_in"))
      (node (ref "U1") (pin "K10") (pinfunction "VSSA_K10") (pintype "power_in"))
      (node (ref "U1") (pin "K11") (pinfunction "VSSA_K11") (pintype "power_in"))
      (node (ref "U1") (pin "K4") (pinfunction "VSSIO_K4") (pintype "power_in"))
      (node (ref "U1") (pin "K5") (pinfunction "VSSIO_K5") (pintype "power_in"))
      (node (ref "U1") (pin "K6") (pinfunction "VSSC_K6") (pintype "power_in"))
      (node (ref "U1") (pin "K9") (pinfunction "VSSD_K9") (pintype "power_in"))
      (node (ref "U1") (pin "M6") (pinfunction "CKINN_M6") (pintype "input"))
      (node (ref "UP2") (pin "2") (pinfunction "GND_2") (pintype "input"))
      (node (ref "UP3") (pin "2") (pinfunction "GND_2") (pintype "input"))
      (node (ref "UP4") (pin "2") (pinfunction "GND_2") (pintype "input"))
    )
    (net (code "40") (name "Net-(U1C-CKSEL)") (class "Default")
      (node (ref "R1") (pin "2") (pinfunction "2_2") (pintype "passive"))
      (node (ref "U1") (pin "F13") (pinfunction "CKSEL_F13") (pintype "input"))
    )
    (net (code "41") (name "Net-(U1C-TPREQACKX)") (class "Default")
      (node (ref "R7") (pin "2") (pinfunction "2_2") (pintype "passive"))
      (node (ref "U1") (pin "D13") (pinfunction "TPREQACKX_D13") (pintype "input"))
    )
    (net (code "42") (name "Net-(U1C-TPREQACKY)") (class "Default")
      (node (ref "R8") (pin "2") (pinfunction "2_2") (pintype "passive"))
      (node (ref "U1") (pin "C13") (pinfunction "TPREQACKY_C13") (pintype "input"))
    )
    (net (code "43") (name "Net-(U1D-R_EXT_A)") (class "Default")
      (node (ref "R9") (pin "2") (pinfunction "2_2") (pintype "passive"))
      (node (ref "U1") (pin "A9") (pinfunction "R_EXT_A_A9") (pintype "bidirectional"))
    )
    (net (code "44") (name "Net-(U1D-R_EXT_B)") (class "Default")
      (node (ref "R10") (pin "1") (pinfunction "1_1") (pintype "passive"))
      (node (ref "U1") (pin "A10") (pinfunction "R_EXT_B_A10") (pintype "bidirectional"))
    )
    (net (code "45") (name "Net-(UP1-SET)") (class "Default")
      (node (ref "C33") (pin "1") (pinfunction "1_1") (pintype "passive"))
      (node (ref "C34") (pin "1") (pinfunction "1_1") (pintype "passive"))
      (node (ref "R11") (pin "1") (pinfunction "1_1") (pintype "passive"))
      (node (ref "UP1") (pin "4") (pinfunction "SET_4") (pintype "input"))
    )
    (net (code "46") (name "Net-(UP4-EN)") (class "Default")
      (node (ref "R12") (pin "1") (pinfunction "1_1") (pintype "passive"))
      (node (ref "R13") (pin "1") (pinfunction "1_1") (pintype "passive"))
      (node (ref "UP4") (pin "3") (pinfunction "EN_3") (pintype "input"))
    )
    (net (code "47") (name "VCC2P4") (class "Default")
      (node (ref "C31") (pin "1") (pinfunction "1_1") (pintype "passive"))
      (node (ref "R12") (pin "2") (pinfunction "2_2") (pintype "passive"))
      (node (ref "UP1") (pin "1") (pinfunction "OUT_1") (pintype "power_in"))
      (node (ref "UP1") (pin "2") (pinfunction "OUT_2") (pintype "power_in"))
      (node (ref "UP1") (pin "3") (pinfunction "OUT_3") (pintype "power_in"))
      (node (ref "UP1") (pin "9") (pinfunction "EP_9") (pintype "power_in"))
      (node (ref "UP2") (pin "1") (pinfunction "VIN_1") (pintype "input"))
      (node (ref "UP3") (pin "1") (pinfunction "VIN_1") (pintype "input"))
      (node (ref "UP4") (pin "1") (pinfunction "VIN_1") (pintype "input"))
    )
    (net (code "48") (name "VCC3P3") (class "Default")
      (node (ref "C30") (pin "1") (pinfunction "1_1") (pintype "passive"))
      (node (ref "J1") (pin "17") (pintype "passive"))
      (node (ref "J1") (pin "19") (pintype "passive"))
      (node (ref "J1") (pin "21") (pintype "passive"))
      (node (ref "J1") (pin "23") (pintype "passive"))
      (node (ref "J1") (pin "25") (pintype "passive"))
      (node (ref "UP1") (pin "5") (pinfunction "VCONTROL_5") (pintype "power_in"))
      (node (ref "UP1") (pin "6") (pinfunction "NC_6") (pintype "passive"))
      (node (ref "UP1") (pin "7") (pinfunction "IN_7") (pintype "power_in"))
      (node (ref "UP1") (pin "8") (pinfunction "IN_8") (pintype "power_in"))
    )
    (net (code "49") (name "VDDA") (class "Default")
      (node (ref "C22") (pin "2") (pinfunction "2_2") (pintype "passive"))
      (node (ref "C23") (pin "2") (pinfunction "2_2") (pintype "passive"))
      (node (ref "C24") (pin "2") (pinfunction "2_2") (pintype "passive"))
      (node (ref "C25") (pin "2") (pinfunction "2_2") (pintype "passive"))
      (node (ref "C26") (pin "2") (pinfunction "2_2") (pintype "passive"))
      (node (ref "C27") (pin "2") (pinfunction "2_2") (pintype "passive"))
      (node (ref "C28") (pin "2") (pinfunction "2_2") (pintype "passive"))
      (node (ref "C29") (pin "2") (pinfunction "2_2") (pintype "passive"))
      (node (ref "TP5") (pin "1") (pinfunction "1_1") (pintype "passive"))
      (node (ref "U1") (pin "B12") (pinfunction "VDDA_B12") (pintype "power_in"))
      (node (ref "U1") (pin "C12") (pinfunction "VDDA_C12") (pintype "power_in"))
      (node (ref "U1") (pin "D12") (pinfunction "VDDA_D12") (pintype "power_in"))
      (node (ref "U1") (pin "E12") (pinfunction "VDDA_E12") (pintype "power_in"))
      (node (ref "U1") (pin "F12") (pinfunction "VDDA_F12") (pintype "power_in"))
      (node (ref "U1") (pin "G12") (pinfunction "VDDA_G12") (pintype "power_in"))
      (node (ref "U1") (pin "H12") (pinfunction "VDDA_H12") (pintype "power_in"))
      (node (ref "U1") (pin "J12") (pinfunction "VDDA_J12") (pintype "power_in"))
      (node (ref "U1") (pin "K12") (pinfunction "VDDA_K12") (pintype "power_in"))
      (node (ref "U1") (pin "M12") (pinfunction "VDDA_M12") (pintype "power_in"))
      (node (ref "UP2") (pin "5") (pinfunction "VOUT_5") (pintype "input"))
    )
    (net (code "50") (name "VDDD") (class "Default")
      (node (ref "C10") (pin "2") (pinfunction "2_2") (pintype "passive"))
      (node (ref "C11") (pin "2") (pinfunction "2_2") (pintype "passive"))
      (node (ref "C12") (pin "2") (pinfunction "2_2") (pintype "passive"))
      (node (ref "C13") (pin "2") (pinfunction "2_2") (pintype "passive"))
      (node (ref "C14") (pin "2") (pinfunction "2_2") (pintype "passive"))
      (node (ref "C32") (pin "2") (pinfunction "2_2") (pintype "passive"))
      (node (ref "C8") (pin "2") (pinfunction "2_2") (pintype "passive"))
      (node (ref "C9") (pin "2") (pinfunction "2_2") (pintype "passive"))
      (node (ref "TP6") (pin "1") (pinfunction "1_1") (pintype "passive"))
      (node (ref "U1") (pin "B8") (pinfunction "VDDD_B8") (pintype "power_in"))
      (node (ref "U1") (pin "C8") (pinfunction "VDDD_C8") (pintype "power_in"))
      (node (ref "U1") (pin "D8") (pinfunction "VDDD_D8") (pintype "power_in"))
      (node (ref "U1") (pin "E8") (pinfunction "VDDD_E8") (pintype "power_in"))
      (node (ref "U1") (pin "F8") (pinfunction "VDDD_F8") (pintype "power_in"))
      (node (ref "U1") (pin "G8") (pinfunction "VDDD_G8") (pintype "power_in"))
      (node (ref "U1") (pin "H8") (pinfunction "VDDD_H8") (pintype "power_in"))
      (node (ref "U1") (pin "J8") (pinfunction "VDDD_J8") (pintype "power_in"))
      (node (ref "U1") (pin "K8") (pinfunction "VDDD_K8") (pintype "power_in"))
      (node (ref "U1") (pin "M8") (pinfunction "VDDD_M8") (pintype "power_in"))
      (node (ref "UP3") (pin "5") (pinfunction "VOUT_5") (pintype "input"))
    )
    (net (code "51") (name "VDD_IO") (class "Default")
      (node (ref "C1") (pin "2") (pinfunction "2_2") (pintype "passive"))
      (node (ref "C15") (pin "2") (pinfunction "2_2") (pintype "passive"))
      (node (ref "C16") (pin "2") (pinfunction "2_2") (pintype "passive"))
      (node (ref "C17") (pin "2") (pinfunction "2_2") (pintype "passive"))
      (node (ref "C18") (pin "2") (pinfunction "2_2") (pintype "passive"))
      (node (ref "C19") (pin "2") (pinfunction "2_2") (pintype "passive"))
      (node (ref "C2") (pin "2") (pinfunction "2_2") (pintype "passive"))
      (node (ref "C20") (pin "2") (pinfunction "2_2") (pintype "passive"))
      (node (ref "C21") (pin "2") (pinfunction "2_2") (pintype "passive"))
      (node (ref "C3") (pin "2") (pinfunction "2_2") (pintype "passive"))
      (node (ref "C35") (pin "2") (pinfunction "2_2") (pintype "passive"))
      (node (ref "C4") (pin "2") (pinfunction "2_2") (pintype "passive"))
      (node (ref "C5") (pin "2") (pinfunction "2_2") (pintype "passive"))
      (node (ref "C6") (pin "2") (pinfunction "2_2") (pintype "passive"))
      (node (ref "C7") (pin "2") (pinfunction "2_2") (pintype "passive"))
      (node (ref "TP7") (pin "1") (pinfunction "1_1") (pintype "passive"))
      (node (ref "U1") (pin "B3") (pinfunction "VDDIO_B3") (pintype "power_in"))
      (node (ref "U1") (pin "B7") (pinfunction "VDDC_B7") (pintype "power_in"))
      (node (ref "U1") (pin "C3") (pinfunction "VDDIO_C3") (pintype "power_in"))
      (node (ref "U1") (pin "C7") (pinfunction "VDDC_C7") (pintype "power_in"))
      (node (ref "U1") (pin "D3") (pinfunction "VDDIO_D3") (pintype "power_in"))
      (node (ref "U1") (pin "D7") (pinfunction "VDDC_D7") (pintype "power_in"))
      (node (ref "U1") (pin "E3") (pinfunction "VDDIO_E3") (pintype "power_in"))
      (node (ref "U1") (pin "E7") (pinfunction "VDDC_E7") (pintype "power_in"))
      (node (ref "U1") (pin "F3") (pinfunction "VDDIO_F3") (pintype "power_in"))
      (node (ref "U1") (pin "F7") (pinfunction "VDDC_F7") (pintype "power_in"))
      (node (ref "U1") (pin "G3") (pinfunction "VDDIO_G3") (pintype "power_in"))
      (node (ref "U1") (pin "G7") (pinfunction "VDDC_G7") (pintype "power_in"))
      (node (ref "U1") (pin "H3") (pinfunction "VDDIO_H3") (pintype "power_in"))
      (node (ref "U1") (pin "H7") (pinfunction "VDDC_H7") (pintype "power_in"))
      (node (ref "U1") (pin "J3") (pinfunction "VDDIO_J3") (pintype "power_in"))
      (node (ref "U1") (pin "J7") (pinfunction "VDDC_J7") (pintype "power_in"))
      (node (ref "U1") (pin "K3") (pinfunction "VDDIO_K3") (pintype "power_in"))
      (node (ref "U1") (pin "K7") (pinfunction "VDDC_K7") (pintype "power_in"))
      (node (ref "U1") (pin "M7") (pinfunction "VDDC_M7") (pintype "power_in"))
      (node (ref "UP4") (pin "5") (pinfunction "VOUT_5") (pintype "input"))
    )
    (net (code "52") (name "unconnected-(H1-Pad0)") (class "Default")
      (node (ref "H1") (pin "0") (pinfunction "0_0") (pintype "passive"))
    )
    (net (code "53") (name "unconnected-(H2-Pad0)") (class "Default")
      (node (ref "H2") (pin "0") (pinfunction "0_0") (pintype "passive"))
    )
    (net (code "54") (name "unconnected-(H3-Pad0)") (class "Default")
      (node (ref "H3") (pin "0") (pinfunction "0_0") (pintype "passive"))
    )
    (net (code "55") (name "unconnected-(H4-Pad0)") (class "Default")
      (node (ref "H4") (pin "0") (pinfunction "0_0") (pintype "passive"))
    )
    (net (code "56") (name "unconnected-(J1-Pad11)") (class "Default")
      (node (ref "J1") (pin "11") (pintype "passive+no_connect"))
    )
    (net (code "57") (name "unconnected-(J1-Pad13)") (class "Default")
      (node (ref "J1") (pin "13") (pintype "passive+no_connect"))
    )
    (net (code "58") (name "unconnected-(J1-Pad15)") (class "Default")
      (node (ref "J1") (pin "15") (pintype "passive+no_connect"))
    )
    (net (code "59") (name "unconnected-(U1D-IPHOTO-PadK13)") (class "Default")
      (node (ref "U1") (pin "K13") (pinfunction "IPHOTO_K13") (pintype "bidirectional+no_connect"))
    )
    (net (code "60") (name "unconnected-(U1D-REFR_CLK-PadG13)") (class "Default")
      (node (ref "U1") (pin "G13") (pinfunction "REFR_CLK_G13") (pintype "output+no_connect"))
    )
    (net (code "61") (name "unconnected-(U1D-TPA1-PadA11)") (class "Default")
      (node (ref "U1") (pin "A11") (pinfunction "TPA1_A11") (pintype "bidirectional+no_connect"))
    )
    (net (code "62") (name "unconnected-(U1D-TPA2-PadA12)") (class "Default")
      (node (ref "U1") (pin "A12") (pinfunction "TPA2_A12") (pintype "bidirectional+no_connect"))
    )
    (net (code "63") (name "unconnected-(U1D-TPA3-PadA13)") (class "Default")
      (node (ref "U1") (pin "A13") (pinfunction "TPA3_A13") (pintype "bidirectional+no_connect"))
    )
    (net (code "64") (name "unconnected-(U1D-TPA4-PadB13)") (class "Default")
      (node (ref "U1") (pin "B13") (pinfunction "TPA4_B13") (pintype "bidirectional+no_connect"))
    )
    (net (code "65") (name "unconnected-(U1D-TPD1-PadA7)") (class "Default")
      (node (ref "U1") (pin "A7") (pinfunction "TPD1_A7") (pintype "output+no_connect"))
    )
    (net (code "66") (name "unconnected-(U1D-TPD2-PadA8)") (class "Default")
      (node (ref "U1") (pin "A8") (pinfunction "TPD2_A8") (pintype "output+no_connect"))
    )
    (net (code "67") (name "unconnected-(UP2-NC-Pad4)") (class "Default")
      (node (ref "UP2") (pin "4") (pinfunction "NC_4") (pintype "input+no_connect"))
    )
    (net (code "68") (name "unconnected-(UP3-NC-Pad4)") (class "Default")
      (node (ref "UP3") (pin "4") (pinfunction "NC_4") (pintype "input+no_connect"))
    )
    (net (code "69") (name "unconnected-(UP4-NC-Pad4)") (class "Default")
      (node (ref "UP4") (pin "4") (pinfunction "NC_4") (pintype "input+no_connect"))
    )
  )
)
